# C210_0007_Sensors_220601.net
KiCad netlist of a schematic drawn in Altium Designer
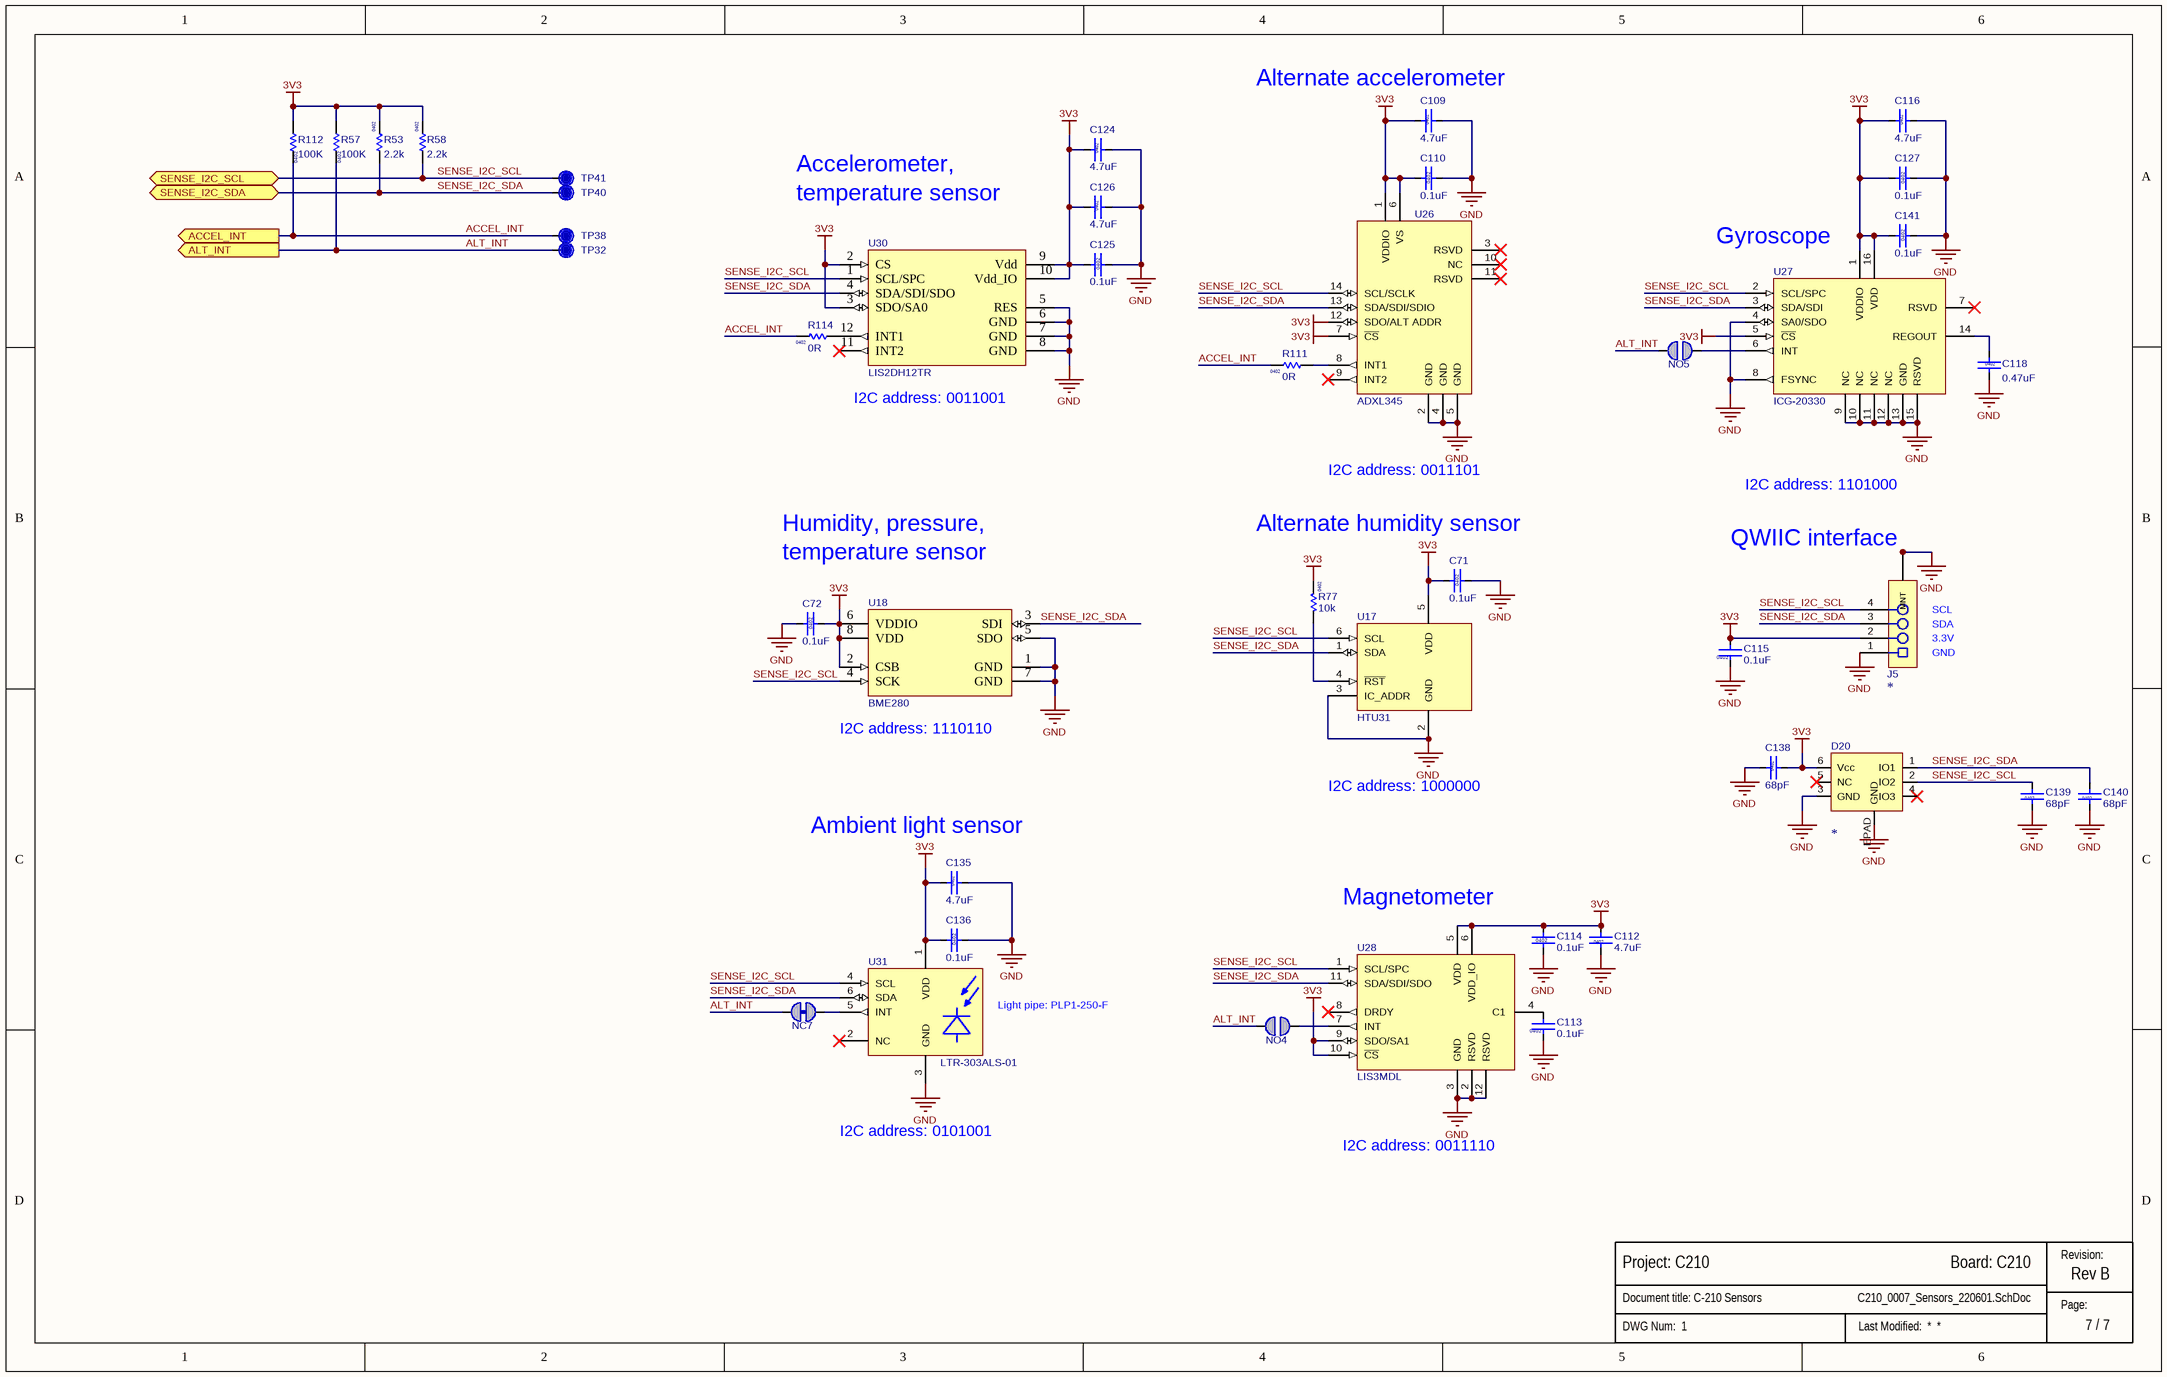
[diagram p0: C210_0007_Sensors_220601.SchDoc]

(export (version "E")
  (design (tool "Eeschema 10.0.6"))
  (components
    (comp (ref "C71")
      (value "0.1uF")
      (footprint "Cap 0402 HD")
      (description "Cap, Ceramic 0.1uF 10V 10% X5R 0402")
      (fields
        (field (name "SIZE") "0402")
        (field (name "PART NUMBER") "120-00016")
        (field (name "MANUFACTURER") "Murata Electronics North America")
      )
      (libsource (lib "Arena_Parts_DB_Lib") (part "Cap Chip"))
    )
    (comp (ref "C72")
      (value "0.1uF")
      (footprint "Cap 0402 HD")
      (description "Cap, Ceramic 0.1uF 10V 10% X5R 0402")
      (fields
        (field (name "SIZE") "0402")
        (field (name "PART NUMBER") "120-00016")
        (field (name "MANUFACTURER") "Murata Electronics North America")
      )
      (libsource (lib "Arena_Parts_DB_Lib") (part "Cap Chip"))
    )
    (comp (ref "C109")
      (value "4.7uF")
      (footprint "Cap 0402 HD")
      (description "Cap, Ceramic 4.7uF 10V 20% X5R 0402")
      (fields
        (field (name "SIZE") "0402")
        (field (name "PART NUMBER") "120-00020")
        (field (name "TOLERANCE") "+/- 20%")
      )
      (libsource (lib "Arena_Parts_DB_Lib") (part "Cap Chip"))
    )
    (comp (ref "C110")
      (value "0.1uF")
      (footprint "Cap 0402 HD")
      (description "Cap, Ceramic 0.1uF 10V 10% X5R 0402")
      (fields
        (field (name "SIZE") "0402")
        (field (name "PART NUMBER") "120-00016")
        (field (name "MANUFACTURER") "Murata Electronics North America")
      )
      (libsource (lib "Arena_Parts_DB_Lib") (part "Cap Chip"))
    )
    (comp (ref "C112")
      (value "4.7uF")
      (footprint "Cap 0402 HD")
      (description "Cap, Ceramic 4.7uF 10V 20% X5R 0402")
      (fields
        (field (name "SIZE") "0402")
        (field (name "PART NUMBER") "120-00020")
        (field (name "TOLERANCE") "+/- 20%")
      )
      (libsource (lib "Arena_Parts_DB_Lib") (part "Cap Chip"))
    )
    (comp (ref "C113")
      (value "0.1uF")
      (footprint "Cap 0402 HD")
      (description "Cap, Ceramic 0.1uF 10V 10% X5R 0402")
      (fields
        (field (name "SIZE") "0402")
        (field (name "PART NUMBER") "120-00016")
        (field (name "MANUFACTURER") "Murata Electronics North America")
      )
      (libsource (lib "Arena_Parts_DB_Lib") (part "Cap Chip"))
    )
    (comp (ref "C114")
      (value "0.1uF")
      (footprint "Cap 0402 HD")
      (description "Cap, Ceramic 0.1uF 10V 10% X5R 0402")
      (fields
        (field (name "SIZE") "0402")
        (field (name "PART NUMBER") "120-00016")
        (field (name "MANUFACTURER") "Murata Electronics North America")
      )
      (libsource (lib "Arena_Parts_DB_Lib") (part "Cap Chip"))
    )
    (comp (ref "C115")
      (value "0.1uF")
      (footprint "Cap 0402 HD")
      (description "Cap, Ceramic 0.1uF 10V 10% X5R 0402")
      (fields
        (field (name "SIZE") "0402")
        (field (name "PART NUMBER") "120-00016")
        (field (name "MANUFACTURER") "Murata Electronics North America")
      )
      (libsource (lib "Arena_Parts_DB_Lib") (part "Cap Chip"))
    )
    (comp (ref "C116")
      (value "4.7uF")
      (footprint "Cap 0402 HD")
      (description "Cap, Ceramic 4.7uF 10V 20% X5R 0402")
      (fields
        (field (name "SIZE") "0402")
        (field (name "PART NUMBER") "120-00020")
        (field (name "TOLERANCE") "+/- 20%")
      )
      (libsource (lib "Arena_Parts_DB_Lib") (part "Cap Chip"))
    )
    (comp (ref "C118")
      (value "0.47uF")
      (footprint "Cap 0402 HD")
      (description "Cap, Ceramic, 0.47UF 10V 10% X5R 0402")
      (fields
        (field (name "SIZE") "0402")
        (field (name "PART NUMBER") "120-00072")
        (field (name "TOLERANCE") "+/- 10%")
      )
      (libsource (lib "Arena_Parts_DB_Lib") (part "Cap Chip"))
    )
    (comp (ref "C124")
      (value "4.7uF")
      (footprint "Cap 0402 HD")
      (description "Cap, Ceramic 4.7uF 10V 20% X5R 0402")
      (fields
        (field (name "SIZE") "0402")
        (field (name "PART NUMBER") "120-00020")
        (field (name "TOLERANCE") "+/- 20%")
      )
      (libsource (lib "Arena_Parts_DB_Lib") (part "Cap Chip"))
    )
    (comp (ref "C125")
      (value "0.1uF")
      (footprint "Cap 0402 HD")
      (description "Cap, Ceramic 0.1uF 10V 10% X5R 0402")
      (fields
        (field (name "SIZE") "0402")
        (field (name "PART NUMBER") "120-00016")
        (field (name "MANUFACTURER") "Murata Electronics North America")
      )
      (libsource (lib "Arena_Parts_DB_Lib") (part "Cap Chip"))
    )
    (comp (ref "C126")
      (value "4.7uF")
      (footprint "Cap 0402 HD")
      (description "Cap, Ceramic 4.7uF 10V 20% X5R 0402")
      (fields
        (field (name "SIZE") "0402")
        (field (name "PART NUMBER") "120-00020")
        (field (name "TOLERANCE") "+/- 20%")
      )
      (libsource (lib "Arena_Parts_DB_Lib") (part "Cap Chip"))
    )
    (comp (ref "C127")
      (value "0.1uF")
      (footprint "Cap 0402 HD")
      (description "Cap, Ceramic 0.1uF 10V 10% X5R 0402")
      (fields
        (field (name "SIZE") "0402")
        (field (name "PART NUMBER") "120-00016")
        (field (name "MANUFACTURER") "Murata Electronics North America")
      )
      (libsource (lib "Arena_Parts_DB_Lib") (part "Cap Chip"))
    )
    (comp (ref "C135")
      (value "4.7uF")
      (footprint "Cap 0402 HD")
      (description "Cap, Ceramic 4.7uF 10V 20% X5R 0402")
      (fields
        (field (name "SIZE") "0402")
        (field (name "PART NUMBER") "120-00020")
        (field (name "TOLERANCE") "+/- 20%")
      )
      (libsource (lib "Arena_Parts_DB_Lib") (part "Cap Chip"))
    )
    (comp (ref "C136")
      (value "0.1uF")
      (footprint "Cap 0402 HD")
      (description "Cap, Ceramic 0.1uF 10V 10% X5R 0402")
      (fields
        (field (name "SIZE") "0402")
        (field (name "PART NUMBER") "120-00016")
        (field (name "MANUFACTURER") "Murata Electronics North America")
      )
      (libsource (lib "Arena_Parts_DB_Lib") (part "Cap Chip"))
    )
    (comp (ref "C138")
      (value "68pF")
      (footprint "Cap 0402 HD")
      (description "Cap, Ceramic, 68pF, 50V, 1%, NP0, 0402")
      (fields
        (field (name "SIZE") "0402")
        (field (name "PART NUMBER") "120-00047")
        (field (name "TOLERANCE") "+/- 1%")
      )
      (libsource (lib "Arena_Parts_DB_Lib") (part "Cap Chip"))
    )
    (comp (ref "C139")
      (value "68pF")
      (footprint "Cap 0402 HD")
      (description "Cap, Ceramic, 68pF, 50V, 1%, NP0, 0402")
      (fields
        (field (name "SIZE") "0402")
        (field (name "PART NUMBER") "120-00047")
        (field (name "TOLERANCE") "+/- 1%")
      )
      (libsource (lib "Arena_Parts_DB_Lib") (part "Cap Chip"))
    )
    (comp (ref "C140")
      (value "68pF")
      (footprint "Cap 0402 HD")
      (description "Cap, Ceramic, 68pF, 50V, 1%, NP0, 0402")
      (fields
        (field (name "SIZE") "0402")
        (field (name "PART NUMBER") "120-00047")
        (field (name "TOLERANCE") "+/- 1%")
      )
      (libsource (lib "Arena_Parts_DB_Lib") (part "Cap Chip"))
    )
    (comp (ref "C141")
      (value "0.1uF")
      (footprint "Cap 0402 HD")
      (description "Cap, Ceramic 0.1uF 10V 10% X5R 0402")
      (fields
        (field (name "SIZE") "0402")
        (field (name "PART NUMBER") "120-00016")
        (field (name "MANUFACTURER") "Murata Electronics North America")
      )
      (libsource (lib "Arena_Parts_DB_Lib") (part "Cap Chip"))
    )
    (comp (ref "D20")
      (value "~")
      (footprint "TPD3E001DRSR")
      (description "TVS Diode, ESD High Speed 3-Channel Array, WSON-6, 3mmX3mm")
      (fields (field (name "VOLTAGE") "5.5V") (field (name "MANUFACTURER P/N") "*"))
      (libsource (lib "TPD3E001DRSR") (part "TPD3E001"))
    )
    (comp (ref "J5")
      (value "SM04B-SRSS-TB(LF)(SN)")
      (footprint "SM04B-SRSS-TB(LF)(SN)")
      (description "Conn, Header, SMD, 1mm Pitch, 4 Pin, R/A, White")
      (fields (field (name "VOLTAGE") "None") (field (name "MANUFACTURER P/N") "*"))
      (libsource (lib "SM04B-SRSS") (part "SM04B-SRSS-TB(LF)(SN)"))
    )
    (comp (ref "NC7")
      (value "Solderbridge-ShortDNP")
      (footprint "Solderbridge-Short")
      (description "Solderbridge-Short")
      (fields (field (name "ADDED BY") "Paul B"))
      (libsource (lib "PCB_Misc") (part "Solderbridge-Short"))
    )
    (comp (ref "NO4")
      (value "Solderbridge-OpenDNP")
      (footprint "Solderbridge-Open")
      (description "Solderbridge-Open")
      (fields (field (name "ADDED BY") "Paul B"))
      (libsource (lib "PCB_Misc") (part "Solderbridge-Open"))
    )
    (comp (ref "NO5")
      (value "Solderbridge-OpenDNP")
      (footprint "Solderbridge-Open")
      (description "Solderbridge-Open")
      (fields (field (name "ADDED BY") "Paul B"))
      (libsource (lib "PCB_Misc") (part "Solderbridge-Open"))
    )
    (comp (ref "R53")
      (value "2.2k")
      (footprint "RES 0402 HD")
      (description "Resistor, 2.2Kohm, 1%, 1/16W, 0402")
      (fields
        (field (name "SIZE") "0402")
        (field (name "PART NUMBER") "180-00023")
        (field (name "POWER") "1/16W")
      )
      (libsource (lib "Arena_Parts_DB_Lib") (part "Res sm"))
    )
    (comp (ref "R57")
      (value "100K")
      (footprint "RES 0402 HD")
      (description "Resistor 100K ohm 1% 1/16W, 0402")
      (fields
        (field (name "SIZE") "0402")
        (field (name "PART NUMBER") "180-00093")
        (field (name "POWER") "1/16W")
      )
      (libsource (lib "Arena_Parts_DB_Lib") (part "Res sm"))
    )
    (comp (ref "R58")
      (value "2.2k")
      (footprint "RES 0402 HD")
      (description "Resistor, 2.2Kohm, 1%, 1/16W, 0402")
      (fields
        (field (name "SIZE") "0402")
        (field (name "PART NUMBER") "180-00023")
        (field (name "POWER") "1/16W")
      )
      (libsource (lib "Arena_Parts_DB_Lib") (part "Res sm"))
    )
    (comp (ref "R77")
      (value "10k")
      (footprint "RES 0402 HD")
      (description "Resistor 10k ohm 1% 1/16W, 0402")
      (fields
        (field (name "SIZE") "0402")
        (field (name "PART NUMBER") "180-00024")
        (field (name "POWER") "1/16W")
      )
      (libsource (lib "Arena_Parts_DB_Lib") (part "Res sm"))
    )
    (comp (ref "R111")
      (value "0R")
      (footprint "RES 0402 HD")
      (description "Resistor 0 ohm 1/16W 0402")
      (fields
        (field (name "SIZE") "0402")
        (field (name "PART NUMBER") "180-00020")
        (field (name "POWER") "1/16W")
      )
      (libsource (lib "Arena_Parts_DB_Lib") (part "Res sm"))
    )
    (comp (ref "R112")
      (value "100K")
      (footprint "RES 0402 HD")
      (description "Resistor 100K ohm 1% 1/16W, 0402")
      (fields
        (field (name "SIZE") "0402")
        (field (name "PART NUMBER") "180-00093")
        (field (name "POWER") "1/16W")
      )
      (libsource (lib "Arena_Parts_DB_Lib") (part "Res sm"))
    )
    (comp (ref "R114")
      (value "0R")
      (footprint "RES 0402 HD")
      (description "Resistor 0 ohm 1/16W 0402")
      (fields
        (field (name "SIZE") "0402")
        (field (name "PART NUMBER") "180-00020")
        (field (name "POWER") "1/16W")
      )
      (libsource (lib "Arena_Parts_DB_Lib") (part "Res sm"))
    )
    (comp (ref "TP32")
      (value "TP")
      (footprint "TP12R")
      (description "Testpoint, Round 1.0mm Dia")
      (fields
        (field (name "PART NUMBER") "TP10R")
        (field (name "ADDED BY") "Jeremy D")
        (field (name "CHECKED BY") "Paul B")
      )
      (libsource (lib "PCB_Misc") (part "TP_R"))
    )
    (comp (ref "TP38")
      (value "TP")
      (footprint "TP12R")
      (description "Testpoint, Round 1.0mm Dia")
      (fields
        (field (name "PART NUMBER") "TP10R")
        (field (name "ADDED BY") "Jeremy D")
        (field (name "CHECKED BY") "Paul B")
      )
      (libsource (lib "PCB_Misc") (part "TP_R"))
    )
    (comp (ref "TP40")
      (value "TP")
      (footprint "TP12R")
      (description "Testpoint, Round 1.0mm Dia")
      (fields
        (field (name "PART NUMBER") "TP10R")
        (field (name "ADDED BY") "Jeremy D")
        (field (name "CHECKED BY") "Paul B")
      )
      (libsource (lib "PCB_Misc") (part "TP_R"))
    )
    (comp (ref "TP41")
      (value "TP")
      (footprint "TP12R")
      (description "Testpoint, Round 1.0mm Dia")
      (fields
        (field (name "PART NUMBER") "TP10R")
        (field (name "ADDED BY") "Jeremy D")
        (field (name "CHECKED BY") "Paul B")
      )
      (libsource (lib "PCB_Misc") (part "TP_R"))
    )
    (comp (ref "U17")
      (value "HTU31")
      (footprint "HTU31")
      (description "SENSOR, Humidity, I2C, SMT, DFN-6 2.5mmX2.5mm")
      (fields (field (name "MANUFACTURER PART NUMBER 1") "HTU31"))
      (libsource (lib "HTU31") (part "HTU31"))
    )
    (comp (ref "U18")
      (value "250-00039")
      (footprint "DFN0.65P-8Pin")
      (description "SENSOR PRESSURE HUMIDITY TEMP")
      (fields
        (field (name "MANUFACTURER P/N") "BME280")
        (field (name "MANUFACTURER") "Bosch Sensortec")
        (field (name "VOLTAGE") "3.6V")
      )
      (libsource (lib "Arena_Lib") (part "BME280"))
    )
    (comp (ref "U26")
      (value "ADXL345")
      (footprint "ADXL345")
      (description "SENSOR, ACCELEROMETER, 3-AXIS, I2C, SMT, +/-16g, LGA-14 3mmX5mm")
      (fields (field (name "MANUFACTURER PART NUMBER 1") "ADXL345"))
      (libsource (lib "ADXL345") (part "ADXL345"))
    )
    (comp (ref "U27")
      (value "ICG-20330")
      (footprint "ICG-20330")
      (description "SENSOR, Gyroscope, I2C, 3-AXIS, 1.7-3.45V, SMT, LGA-16, 3mmX3mm")
      (fields (field (name "MANUFACTURER PART NUMBER 1") "ICG-20330") (field (name "VOLTAGE") "1.9-3.6V"))
      (libsource (lib "ICG-20330") (part "ICG-20330"))
    )
    (comp (ref "U28")
      (value "LIS3MDL")
      (footprint "LIS3MDL")
      (description "SENSOR, MAGNETOMETER, I2C, 3-AXIS, 1.9-3.6V, SMT, LGA-12, 2mmX2mm")
      (fields (field (name "MANUFACTURER PART NUMBER 1") "LIS3MDL") (field (name "VOLTAGE") "1.9-3.6V"))
      (libsource (lib "LIS3MDL") (part "LIS3MDL"))
    )
    (comp (ref "U30")
      (value "250-00008")
      (footprint "LGA0.5P_4x4_12Pin")
      (description "Accelerometer, 2G-16G Max, 12bit, LGA-12")
      (fields
        (field (name "MANUFACTURER P/N") "LIS2DH12TR")
        (field (name "MANUFACTURER") "STMicroelectronics")
        (field (name "VOLTAGE") "3.6V")
      )
      (libsource (lib "Arena_Lib") (part "LIS2DH12"))
    )
    (comp (ref "U31")
      (value "LTR-303ALS-01")
      (footprint "LTR-303ALS-01")
      (description "SENSOR, AMBIENT LIGHT, I2C, SMT, GNSS, DFN-6 2mmX2mm")
      (fields (field (name "MANUFACTURER PART NUMBER 1") "LTR-303ALS-01"))
      (libsource (lib "LTR-303ALS-01") (part "LTR-303ALS-01"))
    )
  )
  (nets
    (net (code "1") (name "/ACCEL_INT") (class "Default")
      (node (ref "R111") (pin "2") (pinfunction "2_2") (pintype "passive"))
      (node (ref "R112") (pin "2") (pinfunction "2_2") (pintype "passive"))
      (node (ref "R114") (pin "2") (pinfunction "2_2") (pintype "passive"))
      (node (ref "TP38") (pin "1") (pintype "passive"))
    )
    (net (code "2") (name "/ALT_INT") (class "Default")
      (node (ref "NC7") (pin "2") (pinfunction "2_2") (pintype "passive"))
      (node (ref "NO4") (pin "2") (pinfunction "2_2") (pintype "passive"))
      (node (ref "NO5") (pin "2") (pinfunction "2_2") (pintype "passive"))
      (node (ref "R57") (pin "2") (pinfunction "2_2") (pintype "passive"))
      (node (ref "TP32") (pin "1") (pintype "passive"))
    )
    (net (code "3") (name "/SENSE_I2C_SCL") (class "Default")
      (node (ref "C139") (pin "2") (pinfunction "2_2") (pintype "passive"))
      (node (ref "D20") (pin "2") (pinfunction "IO2_2") (pintype "passive"))
      (node (ref "J5") (pin "4") (pinfunction "4_4") (pintype "passive"))
      (node (ref "R58") (pin "1") (pinfunction "1_1") (pintype "passive"))
      (node (ref "TP41") (pin "1") (pintype "passive"))
      (node (ref "U17") (pin "6") (pinfunction "SCL_6") (pintype "input"))
      (node (ref "U18") (pin "4") (pinfunction "SCK_4") (pintype "input"))
      (node (ref "U26") (pin "14") (pinfunction "SCL/SCLK_14") (pintype "bidirectional"))
      (node (ref "U27") (pin "2") (pinfunction "SCL/SPC_2") (pintype "input"))
      (node (ref "U28") (pin "1") (pinfunction "SCL/SPC_1") (pintype "input"))
      (node (ref "U30") (pin "1") (pinfunction "SCL/SPC_1") (pintype "input"))
      (node (ref "U31") (pin "4") (pinfunction "SCL_4") (pintype "input"))
    )
    (net (code "4") (name "/SENSE_I2C_SDA") (class "Default")
      (node (ref "C140") (pin "2") (pinfunction "2_2") (pintype "passive"))
      (node (ref "D20") (pin "1") (pinfunction "IO1_1") (pintype "passive"))
      (node (ref "J5") (pin "3") (pinfunction "3_3") (pintype "passive"))
      (node (ref "R53") (pin "1") (pinfunction "1_1") (pintype "passive"))
      (node (ref "TP40") (pin "1") (pintype "passive"))
      (node (ref "U17") (pin "1") (pinfunction "SDA_1") (pintype "bidirectional"))
      (node (ref "U18") (pin "3") (pinfunction "SDI_3") (pintype "bidirectional"))
      (node (ref "U26") (pin "13") (pinfunction "SDA/SDI/SDIO_13") (pintype "bidirectional"))
      (node (ref "U27") (pin "3") (pinfunction "SDA/SDI_3") (pintype "bidirectional"))
      (node (ref "U28") (pin "11") (pinfunction "SDA/SDI/SDO_11") (pintype "bidirectional"))
      (node (ref "U30") (pin "4") (pinfunction "SDA/SDI/SDO_4") (pintype "bidirectional"))
      (node (ref "U31") (pin "6") (pinfunction "SDA_6") (pintype "bidirectional"))
    )
    (net (code "5") (name "3V3") (class "Default")
      (node (ref "C109") (pin "1") (pinfunction "1_1") (pintype "passive"))
      (node (ref "C110") (pin "1") (pinfunction "1_1") (pintype "passive"))
      (node (ref "C112") (pin "2") (pinfunction "2_2") (pintype "passive"))
      (node (ref "C114") (pin "2") (pinfunction "2_2") (pintype "passive"))
      (node (ref "C115") (pin "2") (pinfunction "2_2") (pintype "passive"))
      (node (ref "C116") (pin "1") (pinfunction "1_1") (pintype "passive"))
      (node (ref "C124") (pin "1") (pinfunction "1_1") (pintype "passive"))
      (node (ref "C125") (pin "1") (pinfunction "1_1") (pintype "passive"))
      (node (ref "C126") (pin "1") (pinfunction "1_1") (pintype "passive"))
      (node (ref "C127") (pin "1") (pinfunction "1_1") (pintype "passive"))
      (node (ref "C135") (pin "1") (pinfunction "1_1") (pintype "passive"))
      (node (ref "C136") (pin "1") (pinfunction "1_1") (pintype "passive"))
      (node (ref "C138") (pin "2") (pinfunction "2_2") (pintype "passive"))
      (node (ref "C141") (pin "1") (pinfunction "1_1") (pintype "passive"))
      (node (ref "C71") (pin "1") (pinfunction "1_1") (pintype "passive"))
      (node (ref "C72") (pin "2") (pinfunction "2_2") (pintype "passive"))
      (node (ref "D20") (pin "6") (pinfunction "Vcc_6") (pintype "power_in"))
      (node (ref "J5") (pin "2") (pinfunction "2_2") (pintype "passive"))
      (node (ref "R112") (pin "1") (pinfunction "1_1") (pintype "passive"))
      (node (ref "R53") (pin "2") (pinfunction "2_2") (pintype "passive"))
      (node (ref "R57") (pin "1") (pinfunction "1_1") (pintype "passive"))
      (node (ref "R58") (pin "2") (pinfunction "2_2") (pintype "passive"))
      (node (ref "R77") (pin "2") (pinfunction "2_2") (pintype "passive"))
      (node (ref "U17") (pin "5") (pinfunction "VDD_5") (pintype "power_in"))
      (node (ref "U18") (pin "2") (pinfunction "CSB_2") (pintype "input"))
      (node (ref "U18") (pin "6") (pinfunction "VDDIO_6") (pintype "power_in"))
      (node (ref "U18") (pin "8") (pinfunction "VDD_8") (pintype "power_in"))
      (node (ref "U26") (pin "1") (pinfunction "VDDIO_1") (pintype "power_in"))
      (node (ref "U26") (pin "12") (pinfunction "SDO/ALT_ADDR_12") (pintype "bidirectional"))
      (node (ref "U26") (pin "6") (pinfunction "VS_6") (pintype "power_in"))
      (node (ref "U26") (pin "7") (pinfunction "~{CS}_7") (pintype "input"))
      (node (ref "U27") (pin "1") (pinfunction "VDDIO_1") (pintype "power_in"))
      (node (ref "U27") (pin "16") (pinfunction "VDD_16") (pintype "power_in"))
      (node (ref "U27") (pin "5") (pinfunction "~{CS}_5") (pintype "input"))
      (node (ref "U28") (pin "10") (pinfunction "~{CS}_10") (pintype "input"))
      (node (ref "U28") (pin "5") (pinfunction "VDD_5") (pintype "power_in"))
      (node (ref "U28") (pin "6") (pinfunction "VDD_IO_6") (pintype "power_in"))
      (node (ref "U28") (pin "9") (pinfunction "SDO/SA1_9") (pintype "bidirectional"))
      (node (ref "U30") (pin "10") (pinfunction "Vdd_IO_10") (pintype "power_in"))
      (node (ref "U30") (pin "2") (pinfunction "CS_2") (pintype "input"))
      (node (ref "U30") (pin "3") (pinfunction "SDO/SA0_3") (pintype "bidirectional"))
      (node (ref "U30") (pin "9") (pinfunction "Vdd_9") (pintype "power_in"))
      (node (ref "U31") (pin "1") (pinfunction "VDD_1") (pintype "power_in"))
    )
    (net (code "6") (name "GND") (class "Default")
      (node (ref "C109") (pin "2") (pinfunction "2_2") (pintype "passive"))
      (node (ref "C110") (pin "2") (pinfunction "2_2") (pintype "passive"))
      (node (ref "C112") (pin "1") (pinfunction "1_1") (pintype "passive"))
      (node (ref "C113") (pin "1") (pinfunction "1_1") (pintype "passive"))
      (node (ref "C114") (pin "1") (pinfunction "1_1") (pintype "passive"))
      (node (ref "C115") (pin "1") (pinfunction "1_1") (pintype "passive"))
      (node (ref "C116") (pin "2") (pinfunction "2_2") (pintype "passive"))
      (node (ref "C118") (pin "2") (pinfunction "2_2") (pintype "passive"))
      (node (ref "C124") (pin "2") (pinfunction "2_2") (pintype "passive"))
      (node (ref "C125") (pin "2") (pinfunction "2_2") (pintype "passive"))
      (node (ref "C126") (pin "2") (pinfunction "2_2") (pintype "passive"))
      (node (ref "C127") (pin "2") (pinfunction "2_2") (pintype "passive"))
      (node (ref "C135") (pin "2") (pinfunction "2_2") (pintype "passive"))
      (node (ref "C136") (pin "2") (pinfunction "2_2") (pintype "passive"))
      (node (ref "C138") (pin "1") (pinfunction "1_1") (pintype "passive"))
      (node (ref "C139") (pin "1") (pinfunction "1_1") (pintype "passive"))
      (node (ref "C140") (pin "1") (pinfunction "1_1") (pintype "passive"))
      (node (ref "C141") (pin "2") (pinfunction "2_2") (pintype "passive"))
      (node (ref "C71") (pin "2") (pinfunction "2_2") (pintype "passive"))
      (node (ref "C72") (pin "1") (pinfunction "1_1") (pintype "passive"))
      (node (ref "D20") (pin "3") (pinfunction "GND_3") (pintype "power_in"))
      (node (ref "D20") (pin "EPAD") (pinfunction "GND_EPAD") (pintype "power_in"))
      (node (ref "J5") (pin "1") (pinfunction "1_1") (pintype "passive"))
      (node (ref "J5") (pin "M1") (pinfunction "MNT_M1") (pintype "passive"))
      (node (ref "J5") (pin "M2") (pinfunction "MNT_M2") (pintype "passive"))
      (node (ref "U17") (pin "2") (pinfunction "GND_2") (pintype "power_in"))
      (node (ref "U17") (pin "3") (pinfunction "IC_ADDR_3") (pintype "passive"))
      (node (ref "U18") (pin "1") (pinfunction "GND_1") (pintype "power_in"))
      (node (ref "U18") (pin "5") (pinfunction "SDO_5") (pintype "bidirectional"))
      (node (ref "U18") (pin "7") (pinfunction "GND_7") (pintype "power_in"))
      (node (ref "U26") (pin "2") (pinfunction "GND_2") (pintype "power_in"))
      (node (ref "U26") (pin "4") (pinfunction "GND_4") (pintype "power_in"))
      (node (ref "U26") (pin "5") (pinfunction "GND_5") (pintype "power_in"))
      (node (ref "U27") (pin "10") (pinfunction "NC_10") (pintype "passive"))
      (node (ref "U27") (pin "11") (pinfunction "NC_11") (pintype "passive"))
      (node (ref "U27") (pin "12") (pinfunction "NC_12") (pintype "passive"))
      (node (ref "U27") (pin "13") (pinfunction "GND_13") (pintype "power_in"))
      (node (ref "U27") (pin "15") (pinfunction "RSVD_15") (pintype "passive"))
      (node (ref "U27") (pin "4") (pinfunction "SA0/SDO_4") (pintype "bidirectional"))
      (node (ref "U27") (pin "8") (pinfunction "FSYNC_8") (pintype "output"))
      (node (ref "U27") (pin "9") (pinfunction "NC_9") (pintype "passive"))
      (node (ref "U28") (pin "12") (pinfunction "RSVD_12") (pintype "passive"))
      (node (ref "U28") (pin "2") (pinfunction "RSVD_2") (pintype "passive"))
      (node (ref "U28") (pin "3") (pinfunction "GND_3") (pintype "power_in"))
      (node (ref "U30") (pin "5") (pinfunction "RES_5") (pintype "passive"))
      (node (ref "U30") (pin "6") (pinfunction "GND_6") (pintype "power_in"))
      (node (ref "U30") (pin "7") (pinfunction "GND_7") (pintype "power_in"))
      (node (ref "U30") (pin "8") (pinfunction "GND_8") (pintype "power_in"))
      (node (ref "U31") (pin "3") (pinfunction "GND_3") (pintype "power_in"))
    )
    (net (code "7") (name "Net-(U17-~{RST})") (class "Default")
      (node (ref "R77") (pin "1") (pinfunction "1_1") (pintype "passive"))
      (node (ref "U17") (pin "4") (pinfunction "~{RST}_4") (pintype "input"))
    )
    (net (code "8") (name "Net-(U26-INT1)") (class "Default")
      (node (ref "R111") (pin "1") (pinfunction "1_1") (pintype "passive"))
      (node (ref "U26") (pin "8") (pinfunction "INT1_8") (pintype "output"))
    )
    (net (code "9") (name "Net-(U27-INT)") (class "Default")
      (node (ref "NO5") (pin "1") (pinfunction "1_1") (pintype "passive"))
      (node (ref "U27") (pin "6") (pinfunction "INT_6") (pintype "output"))
    )
    (net (code "10") (name "Net-(U27-REGOUT)") (class "Default")
      (node (ref "C118") (pin "1") (pinfunction "1_1") (pintype "passive"))
      (node (ref "U27") (pin "14") (pinfunction "REGOUT_14") (pintype "passive"))
    )
    (net (code "11") (name "Net-(U28-C1)") (class "Default")
      (node (ref "C113") (pin "2") (pinfunction "2_2") (pintype "passive"))
      (node (ref "U28") (pin "4") (pinfunction "C1_4") (pintype "passive"))
    )
    (net (code "12") (name "Net-(U28-INT)") (class "Default")
      (node (ref "NO4") (pin "1") (pinfunction "1_1") (pintype "passive"))
      (node (ref "U28") (pin "7") (pinfunction "INT_7") (pintype "output"))
    )
    (net (code "13") (name "Net-(U30-INT1)") (class "Default")
      (node (ref "R114") (pin "1") (pinfunction "1_1") (pintype "passive"))
      (node (ref "U30") (pin "12") (pinfunction "INT1_12") (pintype "output"))
    )
    (net (code "14") (name "Net-(U31-INT)") (class "Default")
      (node (ref "NC7") (pin "1") (pinfunction "1_1") (pintype "passive"))
      (node (ref "U31") (pin "5") (pinfunction "INT_5") (pintype "output"))
    )
    (net (code "15") (name "unconnected-(D20-IO3-Pad4)") (class "Default")
      (node (ref "D20") (pin "4") (pinfunction "IO3_4") (pintype "passive+no_connect"))
    )
    (net (code "16") (name "unconnected-(D20-NC-Pad5)") (class "Default")
      (node (ref "D20") (pin "5") (pinfunction "NC_5") (pintype "passive+no_connect"))
    )
    (net (code "17") (name "unconnected-(U26-INT2-Pad9)") (class "Default")
      (node (ref "U26") (pin "9") (pinfunction "INT2_9") (pintype "output+no_connect"))
    )
    (net (code "18") (name "unconnected-(U26-NC-Pad10)") (class "Default")
      (node (ref "U26") (pin "10") (pinfunction "NC_10") (pintype "passive+no_connect"))
    )
    (net (code "19") (name "unconnected-(U26-RSVD-Pad3)") (class "Default")
      (node (ref "U26") (pin "3") (pinfunction "RSVD_3") (pintype "passive+no_connect"))
    )
    (net (code "20") (name "unconnected-(U26-RSVD-Pad11)") (class "Default")
      (node (ref "U26") (pin "11") (pinfunction "RSVD_11") (pintype "passive+no_connect"))
    )
    (net (code "21") (name "unconnected-(U27-RSVD-Pad7)") (class "Default")
      (node (ref "U27") (pin "7") (pinfunction "RSVD_7") (pintype "passive+no_connect"))
    )
    (net (code "22") (name "unconnected-(U28-DRDY-Pad8)") (class "Default")
      (node (ref "U28") (pin "8") (pinfunction "DRDY_8") (pintype "output+no_connect"))
    )
    (net (code "23") (name "unconnected-(U30-INT2-Pad11)") (class "Default")
      (node (ref "U30") (pin "11") (pinfunction "INT2_11") (pintype "output+no_connect"))
    )
    (net (code "24") (name "unconnected-(U31-NC-Pad2)") (class "Default")
      (node (ref "U31") (pin "2") (pinfunction "NC_2") (pintype "passive+no_connect"))
    )
  )
)
